# uShake_CPU.net
KiCad netlist of a schematic drawn in Altium Designer
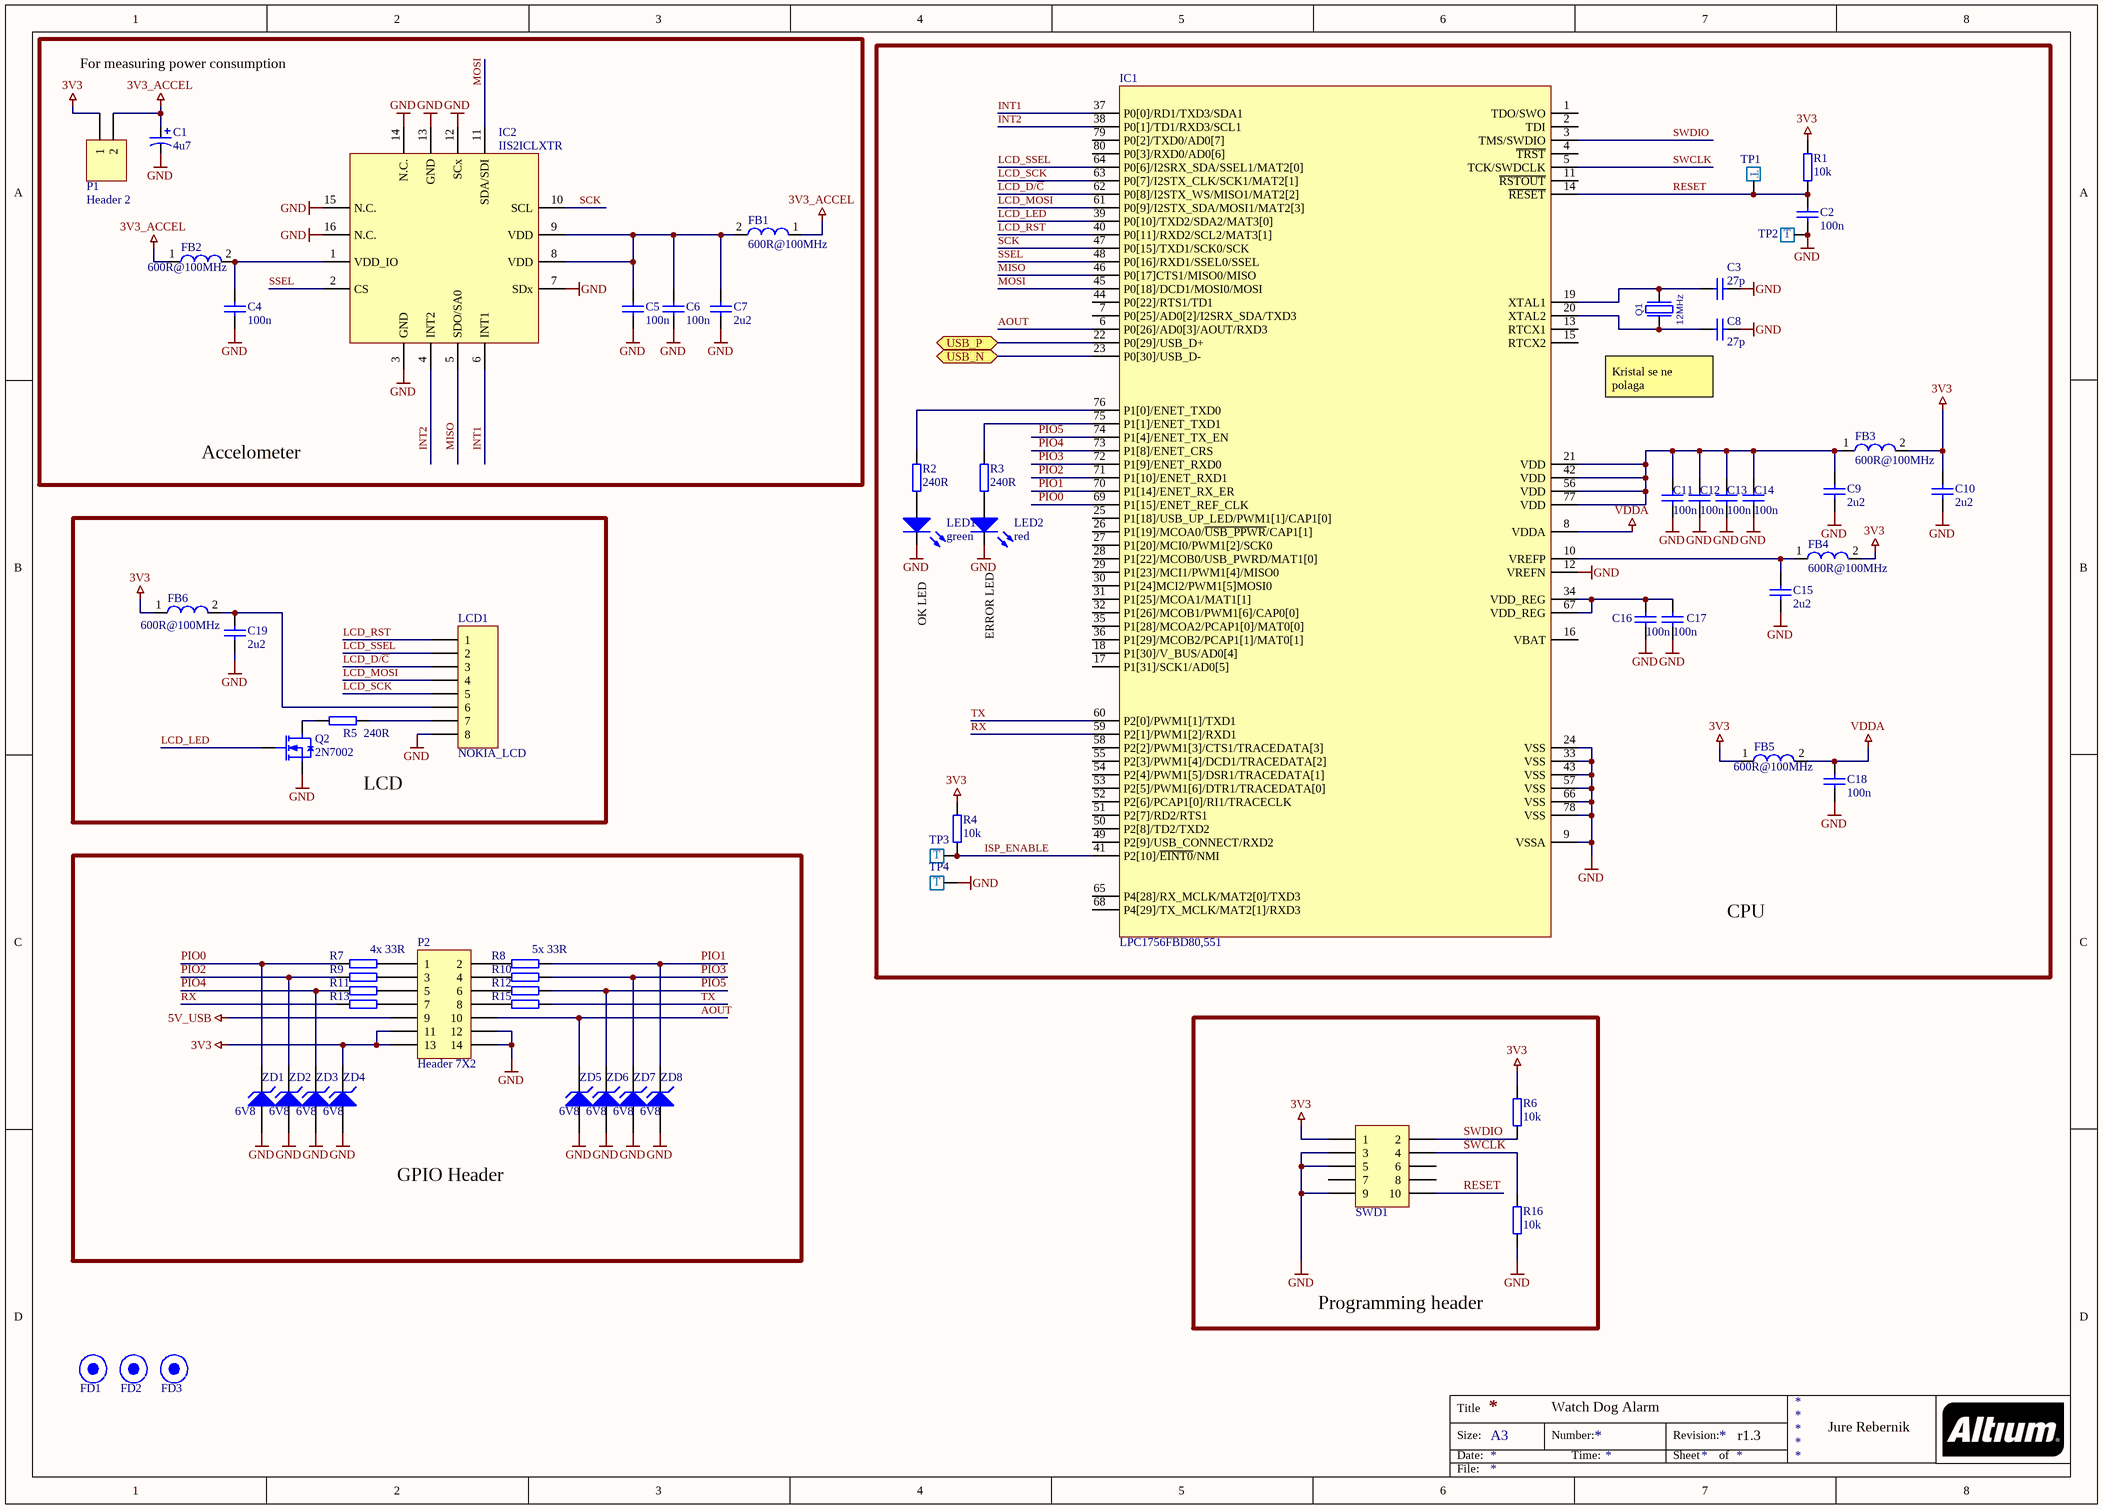
[diagram p0: uShake_CPU.SchDoc]

(export (version "E")
  (design (tool "Eeschema 10.0.6"))
  (components
    (comp (ref "C1")
      (value "4u7")
      (footprint "Tantalum 3216")
      (description "Generic polarized capacitor")
      (libsource (lib "WatchDogAlarm_rev1_3") (part "Capacitor - polarized"))
    )
    (comp (ref "C2")
      (value "100n")
      (footprint "SMD_C0603")
      (description "Capacitor")
      (libsource (lib "WatchDogAlarm_rev1_3") (part "CAP"))
    )
    (comp (ref "C3")
      (value "27p")
      (footprint "SMD_C0603")
      (description "Capacitor")
      (libsource (lib "WatchDogAlarm_rev1_3") (part "CAP"))
    )
    (comp (ref "C4")
      (value "100n")
      (footprint "SMD_C0603")
      (description "Capacitor")
      (libsource (lib "WatchDogAlarm_rev1_3") (part "CAP"))
    )
    (comp (ref "C5")
      (value "100n")
      (footprint "SMD_C0603")
      (description "Capacitor")
      (libsource (lib "WatchDogAlarm_rev1_3") (part "CAP"))
    )
    (comp (ref "C6")
      (value "100n")
      (footprint "SMD_C0603")
      (description "Capacitor")
      (libsource (lib "WatchDogAlarm_rev1_3") (part "CAP"))
    )
    (comp (ref "C7")
      (value "2u2")
      (footprint "SMD_C0805")
      (description "Capacitor")
      (libsource (lib "WatchDogAlarm_rev1_3") (part "CAP"))
    )
    (comp (ref "C8")
      (value "27p")
      (footprint "SMD_C0603")
      (description "Capacitor")
      (libsource (lib "WatchDogAlarm_rev1_3") (part "CAP"))
    )
    (comp (ref "C9")
      (value "2u2")
      (footprint "SMD_C0805")
      (description "Capacitor")
      (libsource (lib "WatchDogAlarm_rev1_3") (part "CAP"))
    )
    (comp (ref "C10")
      (value "2u2")
      (footprint "SMD_C0805")
      (description "Capacitor")
      (libsource (lib "WatchDogAlarm_rev1_3") (part "CAP"))
    )
    (comp (ref "C11")
      (value "100n")
      (footprint "SMD_C0603")
      (description "Capacitor")
      (libsource (lib "WatchDogAlarm_rev1_3") (part "CAP"))
    )
    (comp (ref "C12")
      (value "100n")
      (footprint "SMD_C0603")
      (description "Capacitor")
      (libsource (lib "WatchDogAlarm_rev1_3") (part "CAP"))
    )
    (comp (ref "C13")
      (value "100n")
      (footprint "SMD_C0603")
      (description "Capacitor")
      (libsource (lib "WatchDogAlarm_rev1_3") (part "CAP"))
    )
    (comp (ref "C14")
      (value "100n")
      (footprint "SMD_C0603")
      (description "Capacitor")
      (libsource (lib "WatchDogAlarm_rev1_3") (part "CAP"))
    )
    (comp (ref "C15")
      (value "2u2")
      (footprint "SMD_C0805")
      (description "Capacitor")
      (libsource (lib "WatchDogAlarm_rev1_3") (part "CAP"))
    )
    (comp (ref "C16")
      (value "100n")
      (footprint "SMD_C0603")
      (description "Capacitor")
      (libsource (lib "WatchDogAlarm_rev1_3") (part "CAP"))
    )
    (comp (ref "C17")
      (value "100n")
      (footprint "SMD_C0603")
      (description "Capacitor")
      (libsource (lib "WatchDogAlarm_rev1_3") (part "CAP"))
    )
    (comp (ref "C18")
      (value "100n")
      (footprint "SMD_C0603")
      (description "Capacitor")
      (libsource (lib "WatchDogAlarm_rev1_3") (part "CAP"))
    )
    (comp (ref "C19")
      (value "2u2")
      (footprint "SMD_C0805")
      (description "Capacitor")
      (libsource (lib "WatchDogAlarm_rev1_3") (part "CAP"))
    )
    (comp (ref "FB1")
      (value "600R@100MHz")
      (footprint "SMD_R0603")
      (description "Ferrite bead")
      (libsource (lib "") (part "FB_1"))
    )
    (comp (ref "FB2")
      (value "600R@100MHz")
      (footprint "SMD_R0603")
      (description "Ferrite bead")
      (libsource (lib "WatchDogAlarm_rev1_3") (part "FB"))
    )
    (comp (ref "FB3")
      (value "600R@100MHz")
      (footprint "SMD_R0603")
      (description "Ferrite bead")
      (libsource (lib "WatchDogAlarm_rev1_3") (part "FB"))
    )
    (comp (ref "FB4")
      (value "600R@100MHz")
      (footprint "SMD_R0603")
      (description "Ferrite bead")
      (libsource (lib "WatchDogAlarm_rev1_3") (part "FB"))
    )
    (comp (ref "FB5")
      (value "600R@100MHz")
      (footprint "SMD_R0603")
      (description "Ferrite bead")
      (libsource (lib "WatchDogAlarm_rev1_3") (part "FB"))
    )
    (comp (ref "FB6")
      (value "600R@100MHz")
      (footprint "SMD_R0603")
      (description "Ferrite bead")
      (libsource (lib "WatchDogAlarm_rev1_3") (part "FB"))
    )
    (comp (ref "FD1")
      (value "Fiducial 1mm")
      (footprint "FID1")
      (libsource (lib "WatchDogAlarm_rev1_3") (part "FIDUCIAL"))
    )
    (comp (ref "FD2")
      (value "Fiducial 1mm")
      (footprint "FID1")
      (libsource (lib "WatchDogAlarm_rev1_3") (part "FIDUCIAL"))
    )
    (comp (ref "FD3")
      (value "Fiducial 1mm")
      (footprint "FID1")
      (libsource (lib "WatchDogAlarm_rev1_3") (part "FIDUCIAL"))
    )
    (comp (ref "IC1")
      (value "LPC1756FBD80,551")
      (footprint "WatchDogAlarm_rev1_3:LQFP80")
      (description "LPC1756FBD80")
      (fields (field (name "MANUFACTURER") "NXP"))
      (libsource (lib "WatchDogAlarm_rev1_3") (part "LPC1756FBD80"))
    )
    (comp (ref "IC2")
      (value "IIS2ICLXTR")
      (footprint "LGA-16L")
      (fields (field (name "MANUFACTURER") "STM"))
      (libsource (lib "WatchDogAlarm_SchLib") (part "IIS2ICLXTR"))
    )
    (comp (ref "LCD1")
      (value "NOKIA_LCD")
      (footprint "NOKIA_LCD")
      (libsource (lib "WatchDogAlarm_rev1_3") (part "NOKIA_LCD"))
    )
    (comp (ref "LED1") (value "green") (footprint "SMD_LD0603") (libsource (lib "Atlan") (part "LED")))
    (comp (ref "LED2") (value "red") (footprint "SMD_LD0603") (libsource (lib "Atlan") (part "LED")))
    (comp (ref "P1")
      (value "Header 2")
      (footprint "HDR1X2")
      (description "Header, 2-Pin")
      (fields (field (name "PUBLISHER") "Altium Limited"))
      (libsource (lib "Miscellaneous Connectors") (part "Header 2"))
    )
    (comp (ref "P2")
      (value "Header 7X2")
      (footprint "HDR2X7")
      (description "Header, 7-Pin, Dual row")
      (fields (field (name "PUBLISHER") "Altium Limited"))
      (libsource (lib "WatchDogAlarm_rev1_3") (part "Header 7X2"))
    )
    (comp (ref "Q1")
      (value "12MHz")
      (footprint "QABM3")
      (description "Crystal")
      (fields (field (name "PARTNUMBER") "ABM3-12.000MHZ-D2Y-T") (field (name "MANUFACTURER") "ABRACON"))
      (libsource (lib "WatchDogAlarm_rev1_3") (part "Crystal"))
    )
    (comp (ref "Q2")
      (value "2N7002")
      (footprint "SOT-23")
      (description "Power MOSFET, N Channel, 60 V, 300 mA, 2.8 ohm, SOT-23, Surface Mount")
      (fields (field (name "MANUFACTURER") "NXP"))
      (libsource (lib "WatchDogAlarm_rev1_3") (part "N-MOSFET"))
    )
    (comp (ref "R1")
      (value "10k")
      (footprint "SMD_R0603")
      (libsource (lib "WatchDogAlarm_rev1_3") (part "RESISTOR"))
    )
    (comp (ref "R2")
      (value "240R")
      (footprint "SMD_R0603")
      (libsource (lib "WatchDogAlarm_rev1_3") (part "RESISTOR"))
    )
    (comp (ref "R3")
      (value "240R")
      (footprint "SMD_R0603")
      (libsource (lib "WatchDogAlarm_rev1_3") (part "RESISTOR"))
    )
    (comp (ref "R4")
      (value "10k")
      (footprint "SMD_R0603")
      (libsource (lib "WatchDogAlarm_rev1_3") (part "RESISTOR"))
    )
    (comp (ref "R5")
      (value "240R")
      (footprint "SMD_R0603")
      (libsource (lib "WatchDogAlarm_rev1_3") (part "RESISTOR"))
    )
    (comp (ref "R6")
      (value "10k")
      (footprint "SMD_R0603")
      (libsource (lib "WatchDogAlarm_rev1_3") (part "RESISTOR"))
    )
    (comp (ref "R7")
      (value "33R")
      (footprint "SMD_R0603")
      (libsource (lib "WatchDogAlarm_rev1_3") (part "RESISTOR"))
    )
    (comp (ref "R8")
      (value "33R")
      (footprint "SMD_R0603")
      (libsource (lib "WatchDogAlarm_rev1_3") (part "RESISTOR"))
    )
    (comp (ref "R9")
      (value "33R")
      (footprint "SMD_R0603")
      (libsource (lib "WatchDogAlarm_rev1_3") (part "RESISTOR"))
    )
    (comp (ref "R10")
      (value "33R")
      (footprint "SMD_R0603")
      (libsource (lib "WatchDogAlarm_rev1_3") (part "RESISTOR"))
    )
    (comp (ref "R11")
      (value "33R")
      (footprint "SMD_R0603")
      (libsource (lib "WatchDogAlarm_rev1_3") (part "RESISTOR"))
    )
    (comp (ref "R12")
      (value "33R")
      (footprint "SMD_R0603")
      (libsource (lib "WatchDogAlarm_rev1_3") (part "RESISTOR"))
    )
    (comp (ref "R13")
      (value "33R")
      (footprint "SMD_R0603")
      (libsource (lib "WatchDogAlarm_rev1_3") (part "RESISTOR"))
    )
    (comp (ref "R15")
      (value "33R")
      (footprint "SMD_R0603")
      (libsource (lib "WatchDogAlarm_rev1_3") (part "RESISTOR"))
    )
    (comp (ref "R16")
      (value "10k")
      (footprint "SMD_R0603")
      (libsource (lib "WatchDogAlarm_rev1_3") (part "RESISTOR"))
    )
    (comp (ref "SWD1")
      (value "Header 5x2")
      (footprint "2x5_SWD_CON")
      (description "Header, 5-Pin, Dual row")
      (fields (field (name "MANUFACTURER") "HARWIN") (field (name "PARTNUMBER") "M50-3500542"))
      (libsource (lib "WatchDogAlarm_rev1_3") (part "Header 5X2"))
    )
    (comp (ref "TP1")
      (value "TEST_PAD_1.5mm")
      (footprint "TEST_PAD_1.5mm")
      (libsource (lib "Atlan") (part "TEST_PAD"))
    )
    (comp (ref "TP2")
      (value "TEST_PAD_1.5mm")
      (footprint "TEST_PAD_1.5mm")
      (libsource (lib "Atlan") (part "TEST_PAD"))
    )
    (comp (ref "TP3")
      (value "TEST_PAD_1.5mm")
      (footprint "TEST_PAD_1.5mm")
      (libsource (lib "Atlan") (part "TEST_PAD"))
    )
    (comp (ref "TP4")
      (value "TEST_PAD_1.5mm")
      (footprint "TEST_PAD_1.5mm")
      (libsource (lib "Atlan") (part "TEST_PAD"))
    )
    (comp (ref "ZD1")
      (value "6V8")
      (footprint "SOT-23")
      (description "Zener Diode")
      (fields (field (name "MANUFACTURER") "ON Semiconductor") (field (name "PARTNUMBER") "BZX84C6V8LT1G"))
      (libsource (lib "WatchDogAlarm_rev1_3") (part "ZenerDiode"))
    )
    (comp (ref "ZD2")
      (value "6V8")
      (footprint "SOT-23")
      (description "Zener Diode")
      (fields (field (name "MANUFACTURER") "ON Semiconductor") (field (name "PARTNUMBER") "BZX84C6V8LT1G"))
      (libsource (lib "WatchDogAlarm_rev1_3") (part "ZenerDiode"))
    )
    (comp (ref "ZD3")
      (value "6V8")
      (footprint "SOT-23")
      (description "Zener Diode")
      (fields (field (name "MANUFACTURER") "ON Semiconductor") (field (name "PARTNUMBER") "BZX84C6V8LT1G"))
      (libsource (lib "WatchDogAlarm_rev1_3") (part "ZenerDiode"))
    )
    (comp (ref "ZD4")
      (value "6V8")
      (footprint "SOT-23")
      (description "Zener Diode")
      (fields (field (name "MANUFACTURER") "ON Semiconductor") (field (name "PARTNUMBER") "BZX84C6V8LT1G"))
      (libsource (lib "WatchDogAlarm_rev1_3") (part "ZenerDiode"))
    )
    (comp (ref "ZD5")
      (value "6V8")
      (footprint "SOT-23")
      (description "Zener Diode")
      (fields (field (name "MANUFACTURER") "ON Semiconductor") (field (name "PARTNUMBER") "BZX84C6V8LT1G"))
      (libsource (lib "WatchDogAlarm_rev1_3") (part "ZenerDiode"))
    )
    (comp (ref "ZD6")
      (value "6V8")
      (footprint "SOT-23")
      (description "Zener Diode")
      (fields (field (name "MANUFACTURER") "ON Semiconductor") (field (name "PARTNUMBER") "BZX84C6V8LT1G"))
      (libsource (lib "WatchDogAlarm_rev1_3") (part "ZenerDiode"))
    )
    (comp (ref "ZD7")
      (value "6V8")
      (footprint "SOT-23")
      (description "Zener Diode")
      (fields (field (name "MANUFACTURER") "ON Semiconductor") (field (name "PARTNUMBER") "BZX84C6V8LT1G"))
      (libsource (lib "WatchDogAlarm_rev1_3") (part "ZenerDiode"))
    )
    (comp (ref "ZD8")
      (value "6V8")
      (footprint "SOT-23")
      (description "Zener Diode")
      (fields (field (name "MANUFACTURER") "ON Semiconductor") (field (name "PARTNUMBER") "BZX84C6V8LT1G"))
      (libsource (lib "WatchDogAlarm_rev1_3") (part "ZenerDiode"))
    )
  )
  (nets
    (net (code "1") (name "/AOUT") (class "Default")
      (node (ref "IC1") (pin "6") (pinfunction "P0[26]/AD0[3]/AOUT/RXD3_6") (pintype "passive"))
      (node (ref "P2") (pin "10") (pinfunction "10_10") (pintype "passive"))
      (node (ref "ZD5") (pin "3") (pinfunction "K_3") (pintype "passive"))
    )
    (net (code "2") (name "/INT1") (class "Default")
      (node (ref "IC1") (pin "37") (pinfunction "P0[0]/RD1/TXD3/SDA1_37") (pintype "passive"))
      (node (ref "IC2") (pin "6") (pinfunction "INT1_6") (pintype "passive"))
    )
    (net (code "3") (name "/INT2") (class "Default")
      (node (ref "IC1") (pin "38") (pinfunction "P0[1]/TD1/RXD3/SCL1_38") (pintype "passive"))
      (node (ref "IC2") (pin "4") (pinfunction "INT2_4") (pintype "passive"))
    )
    (net (code "4") (name "/ISP_ENABLE") (class "Default")
      (node (ref "IC1") (pin "41") (pinfunction "P2[10]/~{EINT0}/NMI_41") (pintype "passive"))
      (node (ref "R4") (pin "1") (pintype "passive"))
      (node (ref "TP3") (pin "1") (pintype "passive"))
    )
    (net (code "5") (name "/LCD_D{slash}~{C}") (class "Default")
      (node (ref "IC1") (pin "62") (pinfunction "P0[8]/I2STX_WS/MISO1/MAT2[2]_62") (pintype "passive"))
      (node (ref "LCD1") (pin "3") (pinfunction "3_3") (pintype "passive"))
    )
    (net (code "6") (name "/LCD_LED") (class "Default")
      (node (ref "IC1") (pin "39") (pinfunction "P0[10]/TXD2/SDA2/MAT3[0]_39") (pintype "passive"))
      (node (ref "Q2") (pin "1") (pinfunction "G_1") (pintype "passive"))
    )
    (net (code "7") (name "/LCD_MOSI") (class "Default")
      (node (ref "IC1") (pin "61") (pinfunction "P0[9]/I2STX_SDA/MOSI1/MAT2[3]_61") (pintype "passive"))
      (node (ref "LCD1") (pin "4") (pinfunction "4_4") (pintype "passive"))
    )
    (net (code "8") (name "/LCD_RST") (class "Default")
      (node (ref "IC1") (pin "40") (pinfunction "P0[11]/RXD2/SCL2/MAT3[1]_40") (pintype "passive"))
      (node (ref "LCD1") (pin "1") (pinfunction "1_1") (pintype "passive"))
    )
    (net (code "9") (name "/LCD_SCK") (class "Default")
      (node (ref "IC1") (pin "63") (pinfunction "P0[7]/I2STX_CLK/SCK1/MAT2[1]_63") (pintype "passive"))
      (node (ref "LCD1") (pin "5") (pinfunction "5_5") (pintype "passive"))
    )
    (net (code "10") (name "/LCD_SSEL") (class "Default")
      (node (ref "IC1") (pin "64") (pinfunction "P0[6]/I2SRX_SDA/SSEL1/MAT2[0]_64") (pintype "passive"))
      (node (ref "LCD1") (pin "2") (pinfunction "2_2") (pintype "passive"))
    )
    (net (code "11") (name "/MISO") (class "Default")
      (node (ref "IC1") (pin "46") (pinfunction "P0[17]CTS1/MISO0/MISO_46") (pintype "passive"))
      (node (ref "IC2") (pin "5") (pinfunction "SDO/SA0_5") (pintype "passive"))
    )
    (net (code "12") (name "/MOSI") (class "Default")
      (node (ref "IC1") (pin "45") (pinfunction "P0[18]/DCD1/MOSI0/MOSI_45") (pintype "passive"))
      (node (ref "IC2") (pin "11") (pinfunction "SDA/SDI_11") (pintype "passive"))
    )
    (net (code "13") (name "/PIO0") (class "Default")
      (node (ref "IC1") (pin "69") (pinfunction "P1[15]/ENET_REF_CLK_69") (pintype "passive"))
      (node (ref "R7") (pin "2") (pintype "passive"))
      (node (ref "ZD1") (pin "3") (pinfunction "K_3") (pintype "passive"))
    )
    (net (code "14") (name "/PIO1") (class "Default")
      (node (ref "IC1") (pin "70") (pinfunction "P1[14]/ENET_RX_ER_70") (pintype "passive"))
      (node (ref "R8") (pin "1") (pintype "passive"))
      (node (ref "ZD8") (pin "3") (pinfunction "K_3") (pintype "passive"))
    )
    (net (code "15") (name "/PIO2") (class "Default")
      (node (ref "IC1") (pin "71") (pinfunction "P1[10]/ENET_RXD1_71") (pintype "passive"))
      (node (ref "R9") (pin "2") (pintype "passive"))
      (node (ref "ZD2") (pin "3") (pinfunction "K_3") (pintype "passive"))
    )
    (net (code "16") (name "/PIO3") (class "Default")
      (node (ref "IC1") (pin "72") (pinfunction "P1[9]/ENET_RXD0_72") (pintype "passive"))
      (node (ref "R10") (pin "1") (pintype "passive"))
      (node (ref "ZD7") (pin "3") (pinfunction "K_3") (pintype "passive"))
    )
    (net (code "17") (name "/PIO4") (class "Default")
      (node (ref "IC1") (pin "73") (pinfunction "P1[8]/ENET_CRS_73") (pintype "passive"))
      (node (ref "R11") (pin "2") (pintype "passive"))
      (node (ref "ZD3") (pin "3") (pinfunction "K_3") (pintype "passive"))
    )
    (net (code "18") (name "/PIO5") (class "Default")
      (node (ref "IC1") (pin "74") (pinfunction "P1[4]/ENET_TX_EN_74") (pintype "passive"))
      (node (ref "R12") (pin "1") (pintype "passive"))
      (node (ref "ZD6") (pin "3") (pinfunction "K_3") (pintype "passive"))
    )
    (net (code "19") (name "/RESET") (class "Default")
      (node (ref "C2") (pin "2") (pinfunction "2_2") (pintype "passive"))
      (node (ref "IC1") (pin "14") (pinfunction "~{RESET}_14") (pintype "passive"))
      (node (ref "R1") (pin "1") (pintype "passive"))
      (node (ref "SWD1") (pin "10") (pinfunction "10_10") (pintype "passive"))
      (node (ref "TP1") (pin "1") (pintype "passive"))
    )
    (net (code "20") (name "/RX") (class "Default")
      (node (ref "IC1") (pin "59") (pinfunction "P2[1]/PWM1[2]/RXD1_59") (pintype "passive"))
      (node (ref "R13") (pin "2") (pintype "passive"))
    )
    (net (code "21") (name "/SCK") (class "Default")
      (node (ref "IC1") (pin "47") (pinfunction "P0[15]/TXD1/SCK0/SCK_47") (pintype "passive"))
      (node (ref "IC2") (pin "10") (pinfunction "SCL_10") (pintype "passive"))
    )
    (net (code "22") (name "/SSEL") (class "Default")
      (node (ref "IC1") (pin "48") (pinfunction "P0[16]/RXD1/SSEL0/SSEL_48") (pintype "passive"))
      (node (ref "IC2") (pin "2") (pinfunction "CS_2") (pintype "passive"))
    )
    (net (code "23") (name "/SWCLK") (class "Default")
      (node (ref "IC1") (pin "5") (pinfunction "TCK/SWDCLK_5") (pintype "passive"))
      (node (ref "R16") (pin "2") (pintype "passive"))
      (node (ref "SWD1") (pin "4") (pinfunction "4_4") (pintype "passive"))
    )
    (net (code "24") (name "/SWDIO") (class "Default")
      (node (ref "IC1") (pin "3") (pinfunction "TMS/SWDIO_3") (pintype "passive"))
      (node (ref "R6") (pin "1") (pintype "passive"))
      (node (ref "SWD1") (pin "2") (pinfunction "2_2") (pintype "passive"))
    )
    (net (code "25") (name "/TX") (class "Default")
      (node (ref "IC1") (pin "60") (pinfunction "P2[0]/PWM1[1]/TXD1_60") (pintype "passive"))
      (node (ref "R15") (pin "1") (pintype "passive"))
    )
    (net (code "26") (name "/USB_N") (class "Default")
      (node (ref "IC1") (pin "23") (pinfunction "P0[30]/USB_D-_23") (pintype "passive"))
    )
    (net (code "27") (name "/USB_P") (class "Default")
      (node (ref "IC1") (pin "22") (pinfunction "P0[29]/USB_D+_22") (pintype "passive"))
    )
    (net (code "28") (name "3V3") (class "Default")
      (node (ref "C10") (pin "2") (pinfunction "2_2") (pintype "passive"))
      (node (ref "FB3") (pin "2") (pinfunction "2_2") (pintype "passive"))
      (node (ref "FB4") (pin "2") (pinfunction "2_2") (pintype "passive"))
      (node (ref "FB5") (pin "1") (pinfunction "1_1") (pintype "passive"))
      (node (ref "FB6") (pin "1") (pinfunction "1_1") (pintype "passive"))
      (node (ref "P1") (pin "1") (pinfunction "1_1") (pintype "passive"))
      (node (ref "P2") (pin "11") (pinfunction "11_11") (pintype "passive"))
      (node (ref "P2") (pin "13") (pinfunction "13_13") (pintype "passive"))
      (node (ref "R1") (pin "2") (pintype "passive"))
      (node (ref "R4") (pin "2") (pintype "passive"))
      (node (ref "R6") (pin "2") (pintype "passive"))
      (node (ref "SWD1") (pin "1") (pinfunction "1_1") (pintype "passive"))
      (node (ref "ZD4") (pin "3") (pinfunction "K_3") (pintype "passive"))
    )
    (net (code "29") (name "3V3_ACCEL") (class "Default")
      (node (ref "C1") (pin "1") (pinfunction "1_1") (pintype "passive"))
      (node (ref "FB1") (pin "1") (pinfunction "1_1") (pintype "passive"))
      (node (ref "FB2") (pin "1") (pinfunction "1_1") (pintype "passive"))
      (node (ref "P1") (pin "2") (pinfunction "2_2") (pintype "passive"))
    )
    (net (code "30") (name "5V_USB") (class "Default")
      (node (ref "P2") (pin "9") (pinfunction "9_9") (pintype "passive"))
    )
    (net (code "31") (name "GND") (class "Default")
      (node (ref "C1") (pin "2") (pinfunction "2_2") (pintype "passive"))
      (node (ref "C10") (pin "1") (pinfunction "1_1") (pintype "passive"))
      (node (ref "C11") (pin "1") (pinfunction "1_1") (pintype "passive"))
      (node (ref "C12") (pin "1") (pinfunction "1_1") (pintype "passive"))
      (node (ref "C13") (pin "1") (pinfunction "1_1") (pintype "passive"))
      (node (ref "C14") (pin "1") (pinfunction "1_1") (pintype "passive"))
      (node (ref "C15") (pin "1") (pinfunction "1_1") (pintype "passive"))
      (node (ref "C16") (pin "1") (pinfunction "1_1") (pintype "passive"))
      (node (ref "C17") (pin "1") (pinfunction "1_1") (pintype "passive"))
      (node (ref "C18") (pin "2") (pinfunction "2_2") (pintype "passive"))
      (node (ref "C19") (pin "1") (pinfunction "1_1") (pintype "passive"))
      (node (ref "C2") (pin "1") (pinfunction "1_1") (pintype "passive"))
      (node (ref "C3") (pin "1") (pinfunction "1_1") (pintype "passive"))
      (node (ref "C4") (pin "1") (pinfunction "1_1") (pintype "passive"))
      (node (ref "C5") (pin "1") (pinfunction "1_1") (pintype "passive"))
      (node (ref "C6") (pin "1") (pinfunction "1_1") (pintype "passive"))
      (node (ref "C7") (pin "1") (pinfunction "1_1") (pintype "passive"))
      (node (ref "C8") (pin "1") (pinfunction "1_1") (pintype "passive"))
      (node (ref "C9") (pin "1") (pinfunction "1_1") (pintype "passive"))
      (node (ref "IC1") (pin "12") (pinfunction "VREFN_12") (pintype "passive"))
      (node (ref "IC1") (pin "24") (pinfunction "VSS_24") (pintype "passive"))
      (node (ref "IC1") (pin "33") (pinfunction "VSS_33") (pintype "passive"))
      (node (ref "IC1") (pin "43") (pinfunction "VSS_43") (pintype "passive"))
      (node (ref "IC1") (pin "57") (pinfunction "VSS_57") (pintype "passive"))
      (node (ref "IC1") (pin "66") (pinfunction "VSS_66") (pintype "passive"))
      (node (ref "IC1") (pin "78") (pinfunction "VSS_78") (pintype "passive"))
      (node (ref "IC1") (pin "9") (pinfunction "VSSA_9") (pintype "passive"))
      (node (ref "IC2") (pin "12") (pinfunction "SCx_12") (pintype "passive"))
      (node (ref "IC2") (pin "13") (pinfunction "GND_13") (pintype "passive"))
      (node (ref "IC2") (pin "14") (pinfunction "N.C._14") (pintype "passive"))
      (node (ref "IC2") (pin "15") (pinfunction "N.C._15") (pintype "passive"))
      (node (ref "IC2") (pin "16") (pinfunction "N.C._16") (pintype "passive"))
      (node (ref "IC2") (pin "3") (pinfunction "GND_3") (pintype "passive"))
      (node (ref "IC2") (pin "7") (pinfunction "SDx_7") (pintype "passive"))
      (node (ref "LCD1") (pin "8") (pinfunction "8_8") (pintype "passive"))
      (node (ref "LED1") (pin "1") (pinfunction "K_1") (pintype "passive"))
      (node (ref "LED2") (pin "1") (pinfunction "K_1") (pintype "passive"))
      (node (ref "P2") (pin "12") (pinfunction "12_12") (pintype "passive"))
      (node (ref "P2") (pin "14") (pinfunction "14_14") (pintype "passive"))
      (node (ref "Q2") (pin "2") (pinfunction "S_2") (pintype "passive"))
      (node (ref "R16") (pin "1") (pintype "passive"))
      (node (ref "SWD1") (pin "3") (pinfunction "3_3") (pintype "passive"))
      (node (ref "SWD1") (pin "5") (pinfunction "5_5") (pintype "passive"))
      (node (ref "SWD1") (pin "9") (pinfunction "9_9") (pintype "passive"))
      (node (ref "TP2") (pin "1") (pintype "passive"))
      (node (ref "TP4") (pin "1") (pintype "passive"))
      (node (ref "ZD1") (pin "1") (pinfunction "A_1") (pintype "passive"))
      (node (ref "ZD2") (pin "1") (pinfunction "A_1") (pintype "passive"))
      (node (ref "ZD3") (pin "1") (pinfunction "A_1") (pintype "passive"))
      (node (ref "ZD4") (pin "1") (pinfunction "A_1") (pintype "passive"))
      (node (ref "ZD5") (pin "1") (pinfunction "A_1") (pintype "passive"))
      (node (ref "ZD6") (pin "1") (pinfunction "A_1") (pintype "passive"))
      (node (ref "ZD7") (pin "1") (pinfunction "A_1") (pintype "passive"))
      (node (ref "ZD8") (pin "1") (pinfunction "A_1") (pintype "passive"))
    )
    (net (code "32") (name "Net-(C5-Pad2)") (class "Default")
      (node (ref "C5") (pin "2") (pinfunction "2_2") (pintype "passive"))
      (node (ref "C6") (pin "2") (pinfunction "2_2") (pintype "passive"))
      (node (ref "C7") (pin "2") (pinfunction "2_2") (pintype "passive"))
      (node (ref "FB1") (pin "2") (pinfunction "2_2") (pintype "passive"))
      (node (ref "IC2") (pin "8") (pinfunction "VDD_8") (pintype "passive"))
      (node (ref "IC2") (pin "9") (pinfunction "VDD_9") (pintype "passive"))
    )
    (net (code "33") (name "Net-(C11-Pad2)") (class "Default")
      (node (ref "C11") (pin "2") (pinfunction "2_2") (pintype "passive"))
      (node (ref "C12") (pin "2") (pinfunction "2_2") (pintype "passive"))
      (node (ref "C13") (pin "2") (pinfunction "2_2") (pintype "passive"))
      (node (ref "C14") (pin "2") (pinfunction "2_2") (pintype "passive"))
      (node (ref "C9") (pin "2") (pinfunction "2_2") (pintype "passive"))
      (node (ref "FB3") (pin "1") (pinfunction "1_1") (pintype "passive"))
      (node (ref "IC1") (pin "21") (pinfunction "VDD_21") (pintype "passive"))
      (node (ref "IC1") (pin "42") (pinfunction "VDD_42") (pintype "passive"))
      (node (ref "IC1") (pin "56") (pinfunction "VDD_56") (pintype "passive"))
      (node (ref "IC1") (pin "77") (pinfunction "VDD_77") (pintype "passive"))
    )
    (net (code "34") (name "Net-(C16-Pad2)") (class "Default")
      (node (ref "C16") (pin "2") (pinfunction "2_2") (pintype "passive"))
      (node (ref "C17") (pin "2") (pinfunction "2_2") (pintype "passive"))
      (node (ref "IC1") (pin "34") (pinfunction "VDD_REG_34") (pintype "passive"))
      (node (ref "IC1") (pin "67") (pinfunction "VDD_REG_67") (pintype "passive"))
    )
    (net (code "35") (name "Net-(C19-Pad2)") (class "Default")
      (node (ref "C19") (pin "2") (pinfunction "2_2") (pintype "passive"))
      (node (ref "FB6") (pin "2") (pinfunction "2_2") (pintype "passive"))
      (node (ref "LCD1") (pin "6") (pinfunction "6_6") (pintype "passive"))
    )
    (net (code "36") (name "Net-(IC1-P1[0]{slash}ENET_TXD0)") (class "Default")
      (node (ref "IC1") (pin "76") (pinfunction "P1[0]/ENET_TXD0_76") (pintype "passive"))
      (node (ref "R2") (pin "2") (pintype "passive"))
    )
    (net (code "37") (name "Net-(IC1-P1[1]{slash}ENET_TXD1)") (class "Default")
      (node (ref "IC1") (pin "75") (pinfunction "P1[1]/ENET_TXD1_75") (pintype "passive"))
      (node (ref "R3") (pin "2") (pintype "passive"))
    )
    (net (code "38") (name "Net-(IC1-VREFP)") (class "Default")
      (node (ref "C15") (pin "2") (pinfunction "2_2") (pintype "passive"))
      (node (ref "FB4") (pin "1") (pinfunction "1_1") (pintype "passive"))
      (node (ref "IC1") (pin "10") (pinfunction "VREFP_10") (pintype "passive"))
    )
    (net (code "39") (name "Net-(IC1-XTAL1)") (class "Default")
      (node (ref "C3") (pin "2") (pinfunction "2_2") (pintype "passive"))
      (node (ref "IC1") (pin "19") (pinfunction "XTAL1_19") (pintype "passive"))
      (node (ref "Q1") (pin "1") (pinfunction "1_1") (pintype "passive"))
    )
    (net (code "40") (name "Net-(IC1-XTAL2)") (class "Default")
      (node (ref "C8") (pin "2") (pinfunction "2_2") (pintype "passive"))
      (node (ref "IC1") (pin "20") (pinfunction "XTAL2_20") (pintype "passive"))
      (node (ref "Q1") (pin "2") (pinfunction "2_2") (pintype "passive"))
    )
    (net (code "41") (name "Net-(IC2-VDD_IO)") (class "Default")
      (node (ref "C4") (pin "2") (pinfunction "2_2") (pintype "passive"))
      (node (ref "FB2") (pin "2") (pinfunction "2_2") (pintype "passive"))
      (node (ref "IC2") (pin "1") (pinfunction "VDD_IO_1") (pintype "passive"))
    )
    (net (code "42") (name "Net-(LCD1-Pad7)") (class "Default")
      (node (ref "LCD1") (pin "7") (pinfunction "7_7") (pintype "passive"))
      (node (ref "R5") (pin "1") (pintype "passive"))
    )
    (net (code "43") (name "Net-(LED1-A)") (class "Default")
      (node (ref "LED1") (pin "2") (pinfunction "A_2") (pintype "passive"))
      (node (ref "R2") (pin "1") (pintype "passive"))
    )
    (net (code "44") (name "Net-(LED2-A)") (class "Default")
      (node (ref "LED2") (pin "2") (pinfunction "A_2") (pintype "passive"))
      (node (ref "R3") (pin "1") (pintype "passive"))
    )
    (net (code "45") (name "Net-(P2-Pad1)") (class "Default")
      (node (ref "P2") (pin "1") (pinfunction "1_1") (pintype "passive"))
      (node (ref "R7") (pin "1") (pintype "passive"))
    )
    (net (code "46") (name "Net-(P2-Pad2)") (class "Default")
      (node (ref "P2") (pin "2") (pinfunction "2_2") (pintype "passive"))
      (node (ref "R8") (pin "2") (pintype "passive"))
    )
    (net (code "47") (name "Net-(P2-Pad3)") (class "Default")
      (node (ref "P2") (pin "3") (pinfunction "3_3") (pintype "passive"))
      (node (ref "R9") (pin "1") (pintype "passive"))
    )
    (net (code "48") (name "Net-(P2-Pad4)") (class "Default")
      (node (ref "P2") (pin "4") (pinfunction "4_4") (pintype "passive"))
      (node (ref "R10") (pin "2") (pintype "passive"))
    )
    (net (code "49") (name "Net-(P2-Pad5)") (class "Default")
      (node (ref "P2") (pin "5") (pinfunction "5_5") (pintype "passive"))
      (node (ref "R11") (pin "1") (pintype "passive"))
    )
    (net (code "50") (name "Net-(P2-Pad6)") (class "Default")
      (node (ref "P2") (pin "6") (pinfunction "6_6") (pintype "passive"))
      (node (ref "R12") (pin "2") (pintype "passive"))
    )
    (net (code "51") (name "Net-(P2-Pad7)") (class "Default")
      (node (ref "P2") (pin "7") (pinfunction "7_7") (pintype "passive"))
      (node (ref "R13") (pin "1") (pintype "passive"))
    )
    (net (code "52") (name "Net-(P2-Pad8)") (class "Default")
      (node (ref "P2") (pin "8") (pinfunction "8_8") (pintype "passive"))
      (node (ref "R15") (pin "2") (pintype "passive"))
    )
    (net (code "53") (name "Net-(Q2-D)") (class "Default")
      (node (ref "Q2") (pin "3") (pinfunction "D_3") (pintype "passive"))
      (node (ref "R5") (pin "2") (pintype "passive"))
    )
    (net (code "54") (name "VDDA") (class "Default")
      (node (ref "C18") (pin "1") (pinfunction "1_1") (pintype "passive"))
      (node (ref "FB5") (pin "2") (pinfunction "2_2") (pintype "passive"))
      (node (ref "IC1") (pin "8") (pinfunction "VDDA_8") (pintype "passive"))
    )
    (net (code "55") (name "unconnected-(IC1-P0[2]{slash}TXD0{slash}AD0[7]-Pad79)") (class "Default")
      (node (ref "IC1") (pin "79") (pinfunction "P0[2]/TXD0/AD0[7]_79") (pintype "passive"))
    )
    (net (code "56") (name "unconnected-(IC1-P0[3]{slash}RXD0{slash}AD0[6]-Pad80)") (class "Default")
      (node (ref "IC1") (pin "80") (pinfunction "P0[3]/RXD0/AD0[6]_80") (pintype "passive"))
    )
    (net (code "57") (name "unconnected-(IC1-P0[22]{slash}RTS1{slash}TD1-Pad44)") (class "Default")
      (node (ref "IC1") (pin "44") (pinfunction "P0[22]/RTS1/TD1_44") (pintype "passive"))
    )
    (net (code "58") (name "unconnected-(IC1-P0[25]{slash}AD0[2]{slash}I2SRX_SDA{slash}TXD3-Pad7)") (class "Default")
      (node (ref "IC1") (pin "7") (pinfunction "P0[25]/AD0[2]/I2SRX_SDA/TXD3_7") (pintype "passive"))
    )
    (net (code "59") (name "unconnected-(IC1-P1[18]{slash}USB_UP_LED{slash}PWM1[1]{slash}CAP1[0]-Pad25)") (class "Default")
      (node (ref "IC1") (pin "25") (pinfunction "P1[18]/USB_UP_LED/PWM1[1]/CAP1[0]_25") (pintype "passive"))
    )
    (net (code "60") (name "unconnected-(IC1-P1[19]{slash}MCOA0{slash}~{USB_PPWR}{slash}CAP1[1]-Pad26)") (class "Default")
      (node (ref "IC1") (pin "26") (pinfunction "P1[19]/MCOA0/~{USB_PPWR}/CAP1[1]_26") (pintype "passive"))
    )
    (net (code "61") (name "unconnected-(IC1-P1[20]{slash}MCI0{slash}PWM1[2]{slash}SCK0-Pad27)") (class "Default")
      (node (ref "IC1") (pin "27") (pinfunction "P1[20]/MCI0/PWM1[2]/SCK0_27") (pintype "passive"))
    )
    (net (code "62") (name "unconnected-(IC1-P1[22]{slash}MCOB0{slash}USB_PWRD{slash}MAT1[0]-Pad28)") (class "Default")
      (node (ref "IC1") (pin "28") (pinfunction "P1[22]/MCOB0/USB_PWRD/MAT1[0]_28") (pintype "passive"))
    )
    (net (code "63") (name "unconnected-(IC1-P1[23]{slash}MCI1{slash}PWM1[4]{slash}MISO0-Pad29)") (class "Default")
      (node (ref "IC1") (pin "29") (pinfunction "P1[23]/MCI1/PWM1[4]/MISO0_29") (pintype "passive"))
    )
    (net (code "64") (name "unconnected-(IC1-P1[24]MCI2{slash}PWM1[5]MOSI0-Pad30)") (class "Default")
      (node (ref "IC1") (pin "30") (pinfunction "P1[24]MCI2/PWM1[5]MOSI0_30") (pintype "passive"))
    )
    (net (code "65") (name "unconnected-(IC1-P1[25]{slash}MCOA1{slash}MAT1[1]-Pad31)") (class "Default")
      (node (ref "IC1") (pin "31") (pinfunction "P1[25]/MCOA1/MAT1[1]_31") (pintype "passive"))
    )
    (net (code "66") (name "unconnected-(IC1-P1[26]{slash}MCOB1{slash}PWM1[6]{slash}CAP0[0]-Pad32)") (class "Default")
      (node (ref "IC1") (pin "32") (pinfunction "P1[26]/MCOB1/PWM1[6]/CAP0[0]_32") (pintype "passive"))
    )
    (net (code "67") (name "unconnected-(IC1-P1[28]{slash}MCOA2{slash}PCAP1[0]{slash}MAT0[0]-Pad35)") (class "Default")
      (node (ref "IC1") (pin "35") (pinfunction "P1[28]/MCOA2/PCAP1[0]/MAT0[0]_35") (pintype "passive"))
    )
    (net (code "68") (name "unconnected-(IC1-P1[29]{slash}MCOB2{slash}PCAP1[1]{slash}MAT0[1]-Pad36)") (class "Default")
      (node (ref "IC1") (pin "36") (pinfunction "P1[29]/MCOB2/PCAP1[1]/MAT0[1]_36") (pintype "passive"))
    )
    (net (code "69") (name "unconnected-(IC1-P1[30]{slash}V_BUS{slash}AD0[4]-Pad18)") (class "Default")
      (node (ref "IC1") (pin "18") (pinfunction "P1[30]/V_BUS/AD0[4]_18") (pintype "passive"))
    )
    (net (code "70") (name "unconnected-(IC1-P1[31]{slash}SCK1{slash}AD0[5]-Pad17)") (class "Default")
      (node (ref "IC1") (pin "17") (pinfunction "P1[31]/SCK1/AD0[5]_17") (pintype "passive"))
    )
    (net (code "71") (name "unconnected-(IC1-P2[2]{slash}PWM1[3]{slash}CTS1{slash}TRACEDATA[3]-Pad58)") (class "Default")
      (node (ref "IC1") (pin "58") (pinfunction "P2[2]/PWM1[3]/CTS1/TRACEDATA[3]_58") (pintype "passive"))
    )
    (net (code "72") (name "unconnected-(IC1-P2[3]{slash}PWM1[4]{slash}DCD1{slash}TRACEDATA[2]-Pad55)") (class "Default")
      (node (ref "IC1") (pin "55") (pinfunction "P2[3]/PWM1[4]/DCD1/TRACEDATA[2]_55") (pintype "passive"))
    )
    (net (code "73") (name "unconnected-(IC1-P2[4]{slash}PWM1[5]{slash}DSR1{slash}TRACEDATA[1]-Pad54)") (class "Default")
      (node (ref "IC1") (pin "54") (pinfunction "P2[4]/PWM1[5]/DSR1/TRACEDATA[1]_54") (pintype "passive"))
    )
    (net (code "74") (name "unconnected-(IC1-P2[5]{slash}PWM1[6]{slash}DTR1{slash}TRACEDATA[0]-Pad53)") (class "Default")
      (node (ref "IC1") (pin "53") (pinfunction "P2[5]/PWM1[6]/DTR1/TRACEDATA[0]_53") (pintype "passive"))
    )
    (net (code "75") (name "unconnected-(IC1-P2[6]{slash}PCAP1[0]{slash}RI1{slash}TRACECLK-Pad52)") (class "Default")
      (node (ref "IC1") (pin "52") (pinfunction "P2[6]/PCAP1[0]/RI1/TRACECLK_52") (pintype "passive"))
    )
    (net (code "76") (name "unconnected-(IC1-P2[7]{slash}RD2{slash}RTS1-Pad51)") (class "Default")
      (node (ref "IC1") (pin "51") (pinfunction "P2[7]/RD2/RTS1_51") (pintype "passive"))
    )
    (net (code "77") (name "unconnected-(IC1-P2[8]{slash}TD2{slash}TXD2-Pad50)") (class "Default")
      (node (ref "IC1") (pin "50") (pinfunction "P2[8]/TD2/TXD2_50") (pintype "passive"))
    )
    (net (code "78") (name "unconnected-(IC1-P2[9]{slash}USB_CONNECT{slash}RXD2-Pad49)") (class "Default")
      (node (ref "IC1") (pin "49") (pinfunction "P2[9]/USB_CONNECT/RXD2_49") (pintype "passive"))
    )
    (net (code "79") (name "unconnected-(IC1-P4[28]{slash}RX_MCLK{slash}MAT2[0]{slash}TXD3-Pad65)") (class "Default")
      (node (ref "IC1") (pin "65") (pinfunction "P4[28]/RX_MCLK/MAT2[0]/TXD3_65") (pintype "passive"))
    )
    (net (code "80") (name "unconnected-(IC1-P4[29]{slash}TX_MCLK{slash}MAT2[1]{slash}RXD3-Pad68)") (class "Default")
      (node (ref "IC1") (pin "68") (pinfunction "P4[29]/TX_MCLK/MAT2[1]/RXD3_68") (pintype "passive"))
    )
    (net (code "81") (name "unconnected-(IC1-RTCX1-Pad13)") (class "Default")
      (node (ref "IC1") (pin "13") (pinfunction "RTCX1_13") (pintype "passive"))
    )
    (net (code "82") (name "unconnected-(IC1-RTCX2-Pad15)") (class "Default")
      (node (ref "IC1") (pin "15") (pinfunction "RTCX2_15") (pintype "passive"))
    )
    (net (code "83") (name "unconnected-(IC1-TDI-Pad2)") (class "Default")
      (node (ref "IC1") (pin "2") (pinfunction "TDI_2") (pintype "passive"))
    )
    (net (code "84") (name "unconnected-(IC1-TDO{slash}SWO-Pad1)") (class "Default")
      (node (ref "IC1") (pin "1") (pinfunction "TDO/SWO_1") (pintype "passive"))
    )
    (net (code "85") (name "unconnected-(IC1-VBAT-Pad16)") (class "Default")
      (node (ref "IC1") (pin "16") (pinfunction "VBAT_16") (pintype "passive"))
    )
    (net (code "86") (name "unconnected-(IC1-~{RSTOUT}-Pad11)") (class "Default")
      (node (ref "IC1") (pin "11") (pinfunction "~{RSTOUT}_11") (pintype "passive"))
    )
    (net (code "87") (name "unconnected-(IC1-~{TRST}-Pad4)") (class "Default")
      (node (ref "IC1") (pin "4") (pinfunction "~{TRST}_4") (pintype "passive"))
    )
    (net (code "88") (name "unconnected-(SWD1-Pad6)") (class "Default")
      (node (ref "SWD1") (pin "6") (pinfunction "6_6") (pintype "passive"))
    )
    (net (code "89") (name "unconnected-(SWD1-Pad7)") (class "Default")
      (node (ref "SWD1") (pin "7") (pinfunction "7_7") (pintype "passive"))
    )
    (net (code "90") (name "unconnected-(SWD1-Pad8)") (class "Default")
      (node (ref "SWD1") (pin "8") (pinfunction "8_8") (pintype "passive"))
    )
  )
)
